# Test-plug.net
KiCad netlist of a schematic drawn in EAGLE
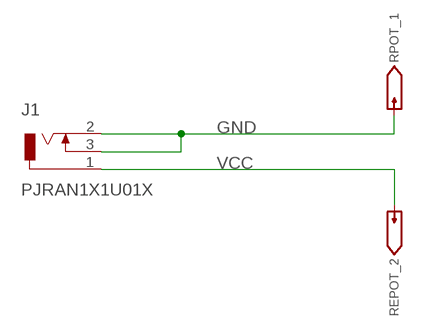
[diagram p0: schematic, sheet 1]

(export (version "E")
  (design (tool "Eeschema 10.0.6"))
  (components
    (comp (ref "J1")
      (value "PJRAN1X1U01X")
      (footprint "eagle-import:PJRAN1X1U01X")
      (fields
        (field (name "DIGIKEY_PART_NUMBER") "PJRAN1X1U01X-ND")
        (field (name "MANUFACTURER") "Switchcraft Inc.")
        (field (name "CREATED_BY") "PCBLayout.com")
      )
      (libsource (lib "eagle-import") (part "PJRAN1X1U01X"))
    )
    (comp (ref "REPOT_2")
      (value "TESTPAD/W_HOLE_1X1")
      (footprint "eagle-import:DIODE_GHI2_TESTPAD_W_HOLE_1X1")
      (libsource (lib "eagle-import") (part "TESTPAD/W_HOLE_1X1"))
    )
    (comp (ref "RPOT_1")
      (value "TESTPAD/W_HOLE_1X1")
      (footprint "eagle-import:DIODE_GHI2_TESTPAD_W_HOLE_1X1")
      (libsource (lib "eagle-import") (part "TESTPAD/W_HOLE_1X1"))
    )
  )
  (nets
    (net (code "1") (name "/GND") (class "Default")
      (node (ref "J1") (pin "2") (pinfunction "2_2") (pintype "passive"))
      (node (ref "J1") (pin "3") (pinfunction "3_3") (pintype "passive"))
      (node (ref "RPOT_1") (pin "P$1") (pinfunction "TP_P$1") (pintype "bidirectional"))
    )
    (net (code "2") (name "/VCC") (class "Default")
      (node (ref "J1") (pin "1") (pinfunction "1_1") (pintype "passive"))
      (node (ref "REPOT_2") (pin "P$1") (pinfunction "TP_P$1") (pintype "bidirectional"))
    )
  )
)
